# Qwiic_PHT_Sensor_-_MS8607.net
KiCad netlist of a schematic drawn in EAGLE
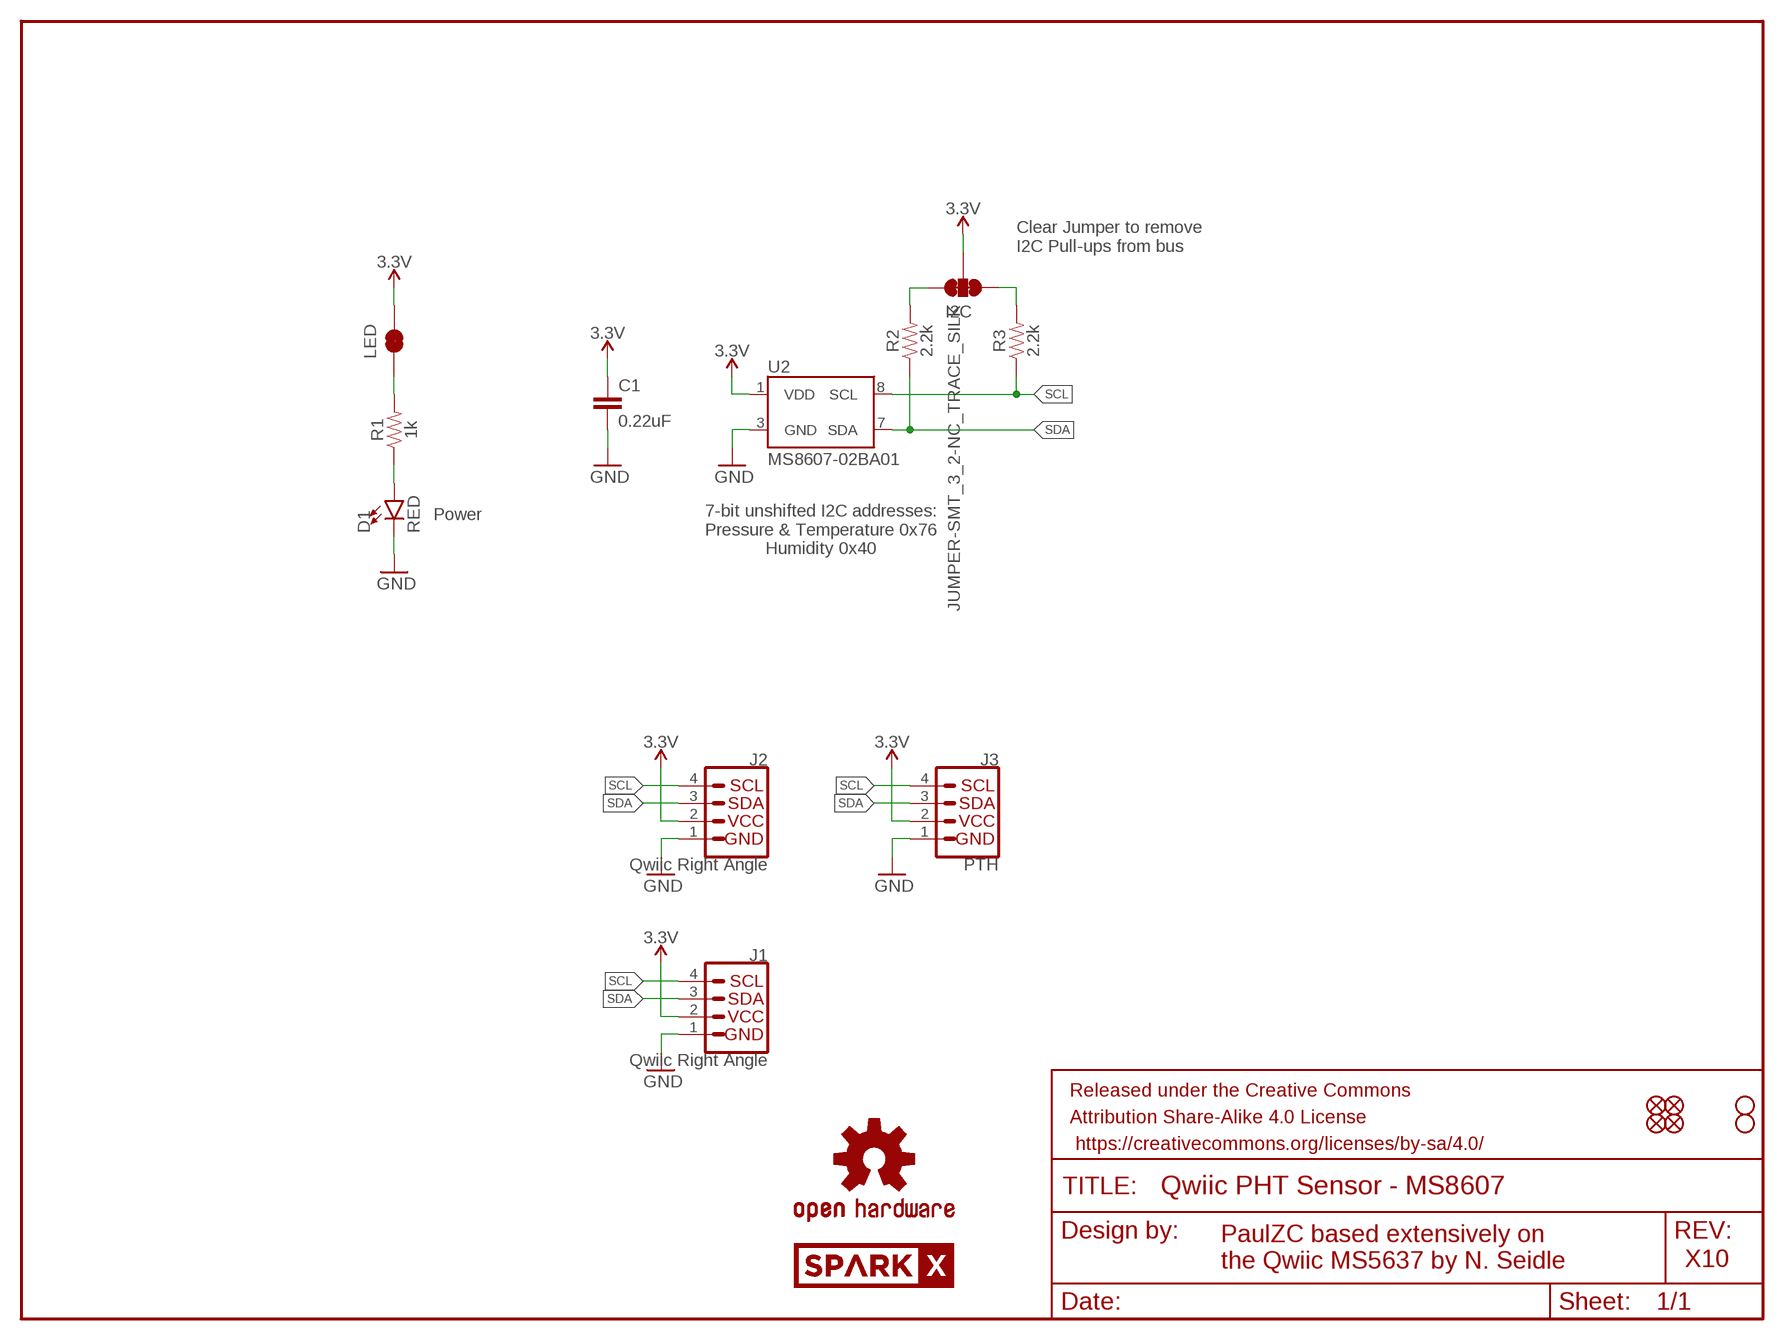
[diagram p0: schematic, sheet 1]

(export (version "E")
  (design (tool "Eeschema 10.0.6"))
  (components
    (comp (ref "C1")
      (value "0.22uF")
      (footprint "eagle-import:0603")
      (libsource (lib "eagle-import") (part "0.22UF-0603-25V-10%"))
    )
    (comp (ref "D1")
      (value "RED")
      (footprint "eagle-import:LED-0603")
      (libsource (lib "eagle-import") (part "LED-RED0603"))
    )
    (comp (ref "FRAME1")
      (value "FRAME-LETTER")
      (footprint "eagle-import:CREATIVE_COMMONS")
      (libsource (lib "eagle-import") (part "FRAME-LETTER"))
    )
    (comp (ref "I2C")
      (value "JUMPER-SMT_3_2-NC_TRACE_SILK")
      (footprint "eagle-import:SMT-JUMPER_3_2-NC_TRACE_SILK")
      (libsource (lib "eagle-import") (part "JUMPER-SMT_3_2-NC_TRACE_SILK"))
    )
    (comp (ref "J1")
      (value "Qwiic Right Angle")
      (footprint "eagle-import:JST04_1MM_RA")
      (libsource (lib "eagle-import") (part "I2C_STANDARDQWIIC"))
    )
    (comp (ref "J2")
      (value "Qwiic Right Angle")
      (footprint "eagle-import:JST04_1MM_RA")
      (libsource (lib "eagle-import") (part "I2C_STANDARDQWIIC"))
    )
    (comp (ref "J3")
      (value "PTH")
      (footprint "eagle-import:1X04_NO_SILK")
      (libsource (lib "eagle-import") (part "SparkX_I2C_STANDARD_NO_SILK"))
    )
    (comp (ref "JP1")
      (value "FIDUCIALUFIDUCIAL")
      (footprint "eagle-import:MICRO-FIDUCIAL")
      (libsource (lib "eagle-import") (part "FIDUCIALUFIDUCIAL"))
    )
    (comp (ref "JP2")
      (value "FIDUCIALUFIDUCIAL")
      (footprint "eagle-import:MICRO-FIDUCIAL")
      (libsource (lib "eagle-import") (part "FIDUCIALUFIDUCIAL"))
    )
    (comp (ref "JP3")
      (value "STAND-OFF")
      (footprint "eagle-import:STAND-OFF")
      (libsource (lib "eagle-import") (part "STAND-OFF"))
    )
    (comp (ref "JP4")
      (value "STAND-OFF")
      (footprint "eagle-import:STAND-OFF")
      (libsource (lib "eagle-import") (part "STAND-OFF"))
    )
    (comp (ref "JP5")
      (value "FIDUCIALUFIDUCIAL")
      (footprint "eagle-import:MICRO-FIDUCIAL")
      (libsource (lib "eagle-import") (part "FIDUCIALUFIDUCIAL"))
    )
    (comp (ref "JP6")
      (value "FIDUCIALUFIDUCIAL")
      (footprint "eagle-import:MICRO-FIDUCIAL")
      (libsource (lib "eagle-import") (part "FIDUCIALUFIDUCIAL"))
    )
    (comp (ref "LED")
      (value "JUMPER-SMT_2_NC_TRACE_SILK")
      (footprint "eagle-import:SMT-JUMPER_2_NC_TRACE_SILK")
      (libsource (lib "eagle-import") (part "JUMPER-SMT_2_NC_TRACE_SILK"))
    )
    (comp (ref "LOGO1")
      (value "OSHW-LOGOMINI")
      (footprint "eagle-import:OSHW-LOGO-MINI")
      (libsource (lib "eagle-import") (part "OSHW-LOGOMINI"))
    )
    (comp (ref "R1")
      (value "1k")
      (footprint "eagle-import:0603")
      (libsource (lib "eagle-import") (part "1KOHM-0603-1/10W-1%"))
    )
    (comp (ref "R2")
      (value "2.2k")
      (footprint "eagle-import:0603")
      (libsource (lib "eagle-import") (part "2.2KOHM-0603-1/10W-1%"))
    )
    (comp (ref "R3")
      (value "2.2k")
      (footprint "eagle-import:0603")
      (libsource (lib "eagle-import") (part "2.2KOHM-0603-1/10W-1%"))
    )
    (comp (ref "U$1")
      (value "SPARKX-LOGO4")
      (footprint "eagle-import:SPARKX-MEDIUM")
      (libsource (lib "eagle-import") (part "SPARKX-LOGO4"))
    )
    (comp (ref "U$2")
      (value "SPARKX-LOGO4")
      (footprint "eagle-import:SPARKX-MEDIUM")
      (libsource (lib "eagle-import") (part "SPARKX-LOGO4"))
    )
    (comp (ref "U2")
      (value "MS8607-02BA01")
      (footprint "eagle-import:MS8607-02BA01")
      (libsource (lib "eagle-import") (part "MS8607-02BA01"))
    )
  )
  (nets
    (net (code "1") (name "3.3V") (class "Default")
      (node (ref "C1") (pin "1") (pinfunction "1_1") (pintype "passive"))
      (node (ref "I2C") (pin "2") (pinfunction "2_2") (pintype "passive"))
      (node (ref "J1") (pin "2") (pinfunction "2_2") (pintype "power_in"))
      (node (ref "J2") (pin "2") (pinfunction "2_2") (pintype "power_in"))
      (node (ref "J3") (pin "2") (pinfunction "VCC_2") (pintype "power_in"))
      (node (ref "LED") (pin "2") (pinfunction "2_2") (pintype "passive"))
      (node (ref "U2") (pin "1") (pinfunction "VDD_1") (pintype "power_in"))
    )
    (net (code "2") (name "GND") (class "Default")
      (node (ref "C1") (pin "2") (pinfunction "2_2") (pintype "passive"))
      (node (ref "D1") (pin "C") (pinfunction "C_C") (pintype "passive"))
      (node (ref "J1") (pin "1") (pinfunction "1_1") (pintype "power_in"))
      (node (ref "J2") (pin "1") (pinfunction "1_1") (pintype "power_in"))
      (node (ref "J3") (pin "1") (pinfunction "GND_1") (pintype "power_in"))
      (node (ref "U2") (pin "3") (pinfunction "GND_3") (pintype "power_in"))
    )
    (net (code "3") (name "Net-(D1-PadA)") (class "Default")
      (node (ref "D1") (pin "A") (pinfunction "A_A") (pintype "passive"))
      (node (ref "R1") (pin "1") (pinfunction "1_1") (pintype "passive"))
    )
    (net (code "4") (name "Net-(I2C-Pad1)") (class "Default")
      (node (ref "I2C") (pin "1") (pinfunction "1_1") (pintype "passive"))
      (node (ref "R3") (pin "2") (pinfunction "2_2") (pintype "passive"))
    )
    (net (code "5") (name "Net-(I2C-Pad3)") (class "Default")
      (node (ref "I2C") (pin "3") (pinfunction "3_3") (pintype "passive"))
      (node (ref "R2") (pin "2") (pinfunction "2_2") (pintype "passive"))
    )
    (net (code "6") (name "Net-(LED-Pad1)") (class "Default")
      (node (ref "LED") (pin "1") (pinfunction "1_1") (pintype "passive"))
      (node (ref "R1") (pin "2") (pinfunction "2_2") (pintype "passive"))
    )
    (net (code "7") (name "SCL") (class "Default")
      (node (ref "J1") (pin "4") (pinfunction "4_4") (pintype "passive"))
      (node (ref "J2") (pin "4") (pinfunction "4_4") (pintype "passive"))
      (node (ref "J3") (pin "4") (pinfunction "SCL_4") (pintype "passive"))
      (node (ref "R3") (pin "1") (pinfunction "1_1") (pintype "passive"))
      (node (ref "U2") (pin "8") (pinfunction "SCL_8") (pintype "bidirectional"))
    )
    (net (code "8") (name "SDA") (class "Default")
      (node (ref "J1") (pin "3") (pinfunction "3_3") (pintype "passive"))
      (node (ref "J2") (pin "3") (pinfunction "3_3") (pintype "passive"))
      (node (ref "J3") (pin "3") (pinfunction "SDA_3") (pintype "passive"))
      (node (ref "R2") (pin "1") (pinfunction "1_1") (pintype "passive"))
      (node (ref "U2") (pin "7") (pinfunction "SDA_7") (pintype "bidirectional"))
    )
  )
)
